# Nintendo_64.net
KiCad netlist of a schematic drawn in EAGLE
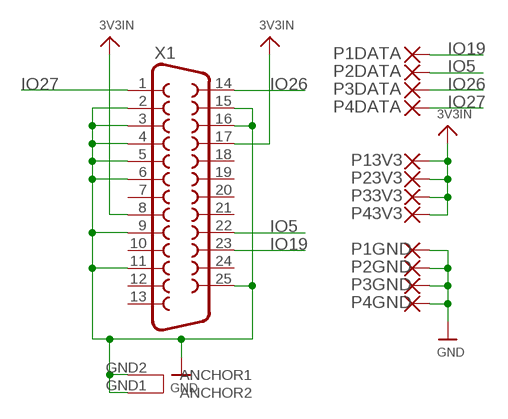
[diagram p0: schematic, sheet 1]

(export (version "E")
  (design (tool "Eeschema 10.0.6"))
  (components
    (comp (ref "P1DATA")
      (value "SMD5")
      (footprint "eagle-import:SMD2,54-5,08")
      (libsource (lib "eagle-import") (part "SMD5"))
    )
    (comp (ref "P1GND")
      (value "SMD5")
      (footprint "eagle-import:SMD2,54-5,08")
      (libsource (lib "eagle-import") (part "SMD5"))
    )
    (comp (ref "P2DATA")
      (value "SMD5")
      (footprint "eagle-import:SMD2,54-5,08")
      (libsource (lib "eagle-import") (part "SMD5"))
    )
    (comp (ref "P2GND")
      (value "SMD5")
      (footprint "eagle-import:SMD2,54-5,08")
      (libsource (lib "eagle-import") (part "SMD5"))
    )
    (comp (ref "P3DATA")
      (value "SMD5")
      (footprint "eagle-import:SMD2,54-5,08")
      (libsource (lib "eagle-import") (part "SMD5"))
    )
    (comp (ref "P3GND")
      (value "SMD5")
      (footprint "eagle-import:SMD2,54-5,08")
      (libsource (lib "eagle-import") (part "SMD5"))
    )
    (comp (ref "P4DATA")
      (value "SMD5")
      (footprint "eagle-import:SMD2,54-5,08")
      (libsource (lib "eagle-import") (part "SMD5"))
    )
    (comp (ref "P4GND")
      (value "SMD5")
      (footprint "eagle-import:SMD2,54-5,08")
      (libsource (lib "eagle-import") (part "SMD5"))
    )
    (comp (ref "P13V3")
      (value "SMD5")
      (footprint "eagle-import:SMD2,54-5,08")
      (libsource (lib "eagle-import") (part "SMD5"))
    )
    (comp (ref "P23V3")
      (value "SMD5")
      (footprint "eagle-import:SMD2,54-5,08")
      (libsource (lib "eagle-import") (part "SMD5"))
    )
    (comp (ref "P33V3")
      (value "SMD5")
      (footprint "eagle-import:SMD2,54-5,08")
      (libsource (lib "eagle-import") (part "SMD5"))
    )
    (comp (ref "P43V3")
      (value "SMD5")
      (footprint "eagle-import:SMD2,54-5,08")
      (libsource (lib "eagle-import") (part "SMD5"))
    )
    (comp (ref "X1")
      (value "DB25_FEMALEHP")
      (footprint "eagle-import:F25HP")
      (libsource (lib "eagle-import") (part "DB25_FEMALEHP"))
    )
  )
  (nets
    (net (code "1") (name "/IO5") (class "Default")
      (node (ref "P2DATA") (pin "1") (pinfunction "P_1") (pintype "passive"))
      (node (ref "X1") (pin "22") (pinfunction "22_22") (pintype "passive"))
    )
    (net (code "2") (name "/IO19") (class "Default")
      (node (ref "P1DATA") (pin "1") (pinfunction "P_1") (pintype "passive"))
      (node (ref "X1") (pin "23") (pinfunction "23_23") (pintype "passive"))
    )
    (net (code "3") (name "/IO26") (class "Default")
      (node (ref "P3DATA") (pin "1") (pinfunction "P_1") (pintype "passive"))
      (node (ref "X1") (pin "14") (pinfunction "14_14") (pintype "passive"))
    )
    (net (code "4") (name "/IO27") (class "Default")
      (node (ref "P4DATA") (pin "1") (pinfunction "P_1") (pintype "passive"))
      (node (ref "X1") (pin "1") (pinfunction "1_1") (pintype "passive"))
    )
    (net (code "5") (name "3V3IN") (class "Default")
      (node (ref "P13V3") (pin "1") (pinfunction "P_1") (pintype "passive"))
      (node (ref "P23V3") (pin "1") (pinfunction "P_1") (pintype "passive"))
      (node (ref "P33V3") (pin "1") (pinfunction "P_1") (pintype "passive"))
      (node (ref "P43V3") (pin "1") (pinfunction "P_1") (pintype "passive"))
      (node (ref "X1") (pin "17") (pinfunction "17_17") (pintype "passive"))
      (node (ref "X1") (pin "8") (pinfunction "8_8") (pintype "passive"))
    )
    (net (code "6") (name "GND") (class "Default")
      (node (ref "P1GND") (pin "1") (pinfunction "P_1") (pintype "passive"))
      (node (ref "P2GND") (pin "1") (pinfunction "P_1") (pintype "passive"))
      (node (ref "P3GND") (pin "1") (pinfunction "P_1") (pintype "passive"))
      (node (ref "P4GND") (pin "1") (pinfunction "P_1") (pintype "passive"))
      (node (ref "X1") (pin "11") (pinfunction "11_11") (pintype "passive"))
      (node (ref "X1") (pin "15") (pinfunction "15_15") (pintype "passive"))
      (node (ref "X1") (pin "16") (pinfunction "16_16") (pintype "passive"))
      (node (ref "X1") (pin "2") (pinfunction "2_2") (pintype "passive"))
      (node (ref "X1") (pin "25") (pinfunction "25_25") (pintype "passive"))
      (node (ref "X1") (pin "3") (pinfunction "3_3") (pintype "passive"))
      (node (ref "X1") (pin "4") (pinfunction "4_4") (pintype "passive"))
      (node (ref "X1") (pin "5") (pinfunction "5_5") (pintype "passive"))
      (node (ref "X1") (pin "6") (pinfunction "6_6") (pintype "passive"))
      (node (ref "X1") (pin "9") (pinfunction "9_9") (pintype "passive"))
      (node (ref "X1") (pin "GND1") (pinfunction "ANCHOR2_GND1") (pintype "bidirectional"))
      (node (ref "X1") (pin "GND2") (pinfunction "ANCHOR1_GND2") (pintype "bidirectional"))
    )
    (net (code "7") (name "unconnected-(X1-Pad7)") (class "Default")
      (node (ref "X1") (pin "7") (pinfunction "7_7") (pintype "passive"))
    )
    (net (code "8") (name "unconnected-(X1-Pad10)") (class "Default")
      (node (ref "X1") (pin "10") (pinfunction "10_10") (pintype "passive"))
    )
    (net (code "9") (name "unconnected-(X1-Pad12)") (class "Default")
      (node (ref "X1") (pin "12") (pinfunction "12_12") (pintype "passive"))
    )
    (net (code "10") (name "unconnected-(X1-Pad13)") (class "Default")
      (node (ref "X1") (pin "13") (pinfunction "13_13") (pintype "passive"))
    )
    (net (code "11") (name "unconnected-(X1-Pad18)") (class "Default")
      (node (ref "X1") (pin "18") (pinfunction "18_18") (pintype "passive"))
    )
    (net (code "12") (name "unconnected-(X1-Pad19)") (class "Default")
      (node (ref "X1") (pin "19") (pinfunction "19_19") (pintype "passive"))
    )
    (net (code "13") (name "unconnected-(X1-Pad20)") (class "Default")
      (node (ref "X1") (pin "20") (pinfunction "20_20") (pintype "passive"))
    )
    (net (code "14") (name "unconnected-(X1-Pad21)") (class "Default")
      (node (ref "X1") (pin "21") (pinfunction "21_21") (pintype "passive"))
    )
    (net (code "15") (name "unconnected-(X1-Pad24)") (class "Default")
      (node (ref "X1") (pin "24") (pinfunction "24_24") (pintype "passive"))
    )
  )
)
